# keypad.net
KiCad netlist of a schematic drawn in Altium Designer
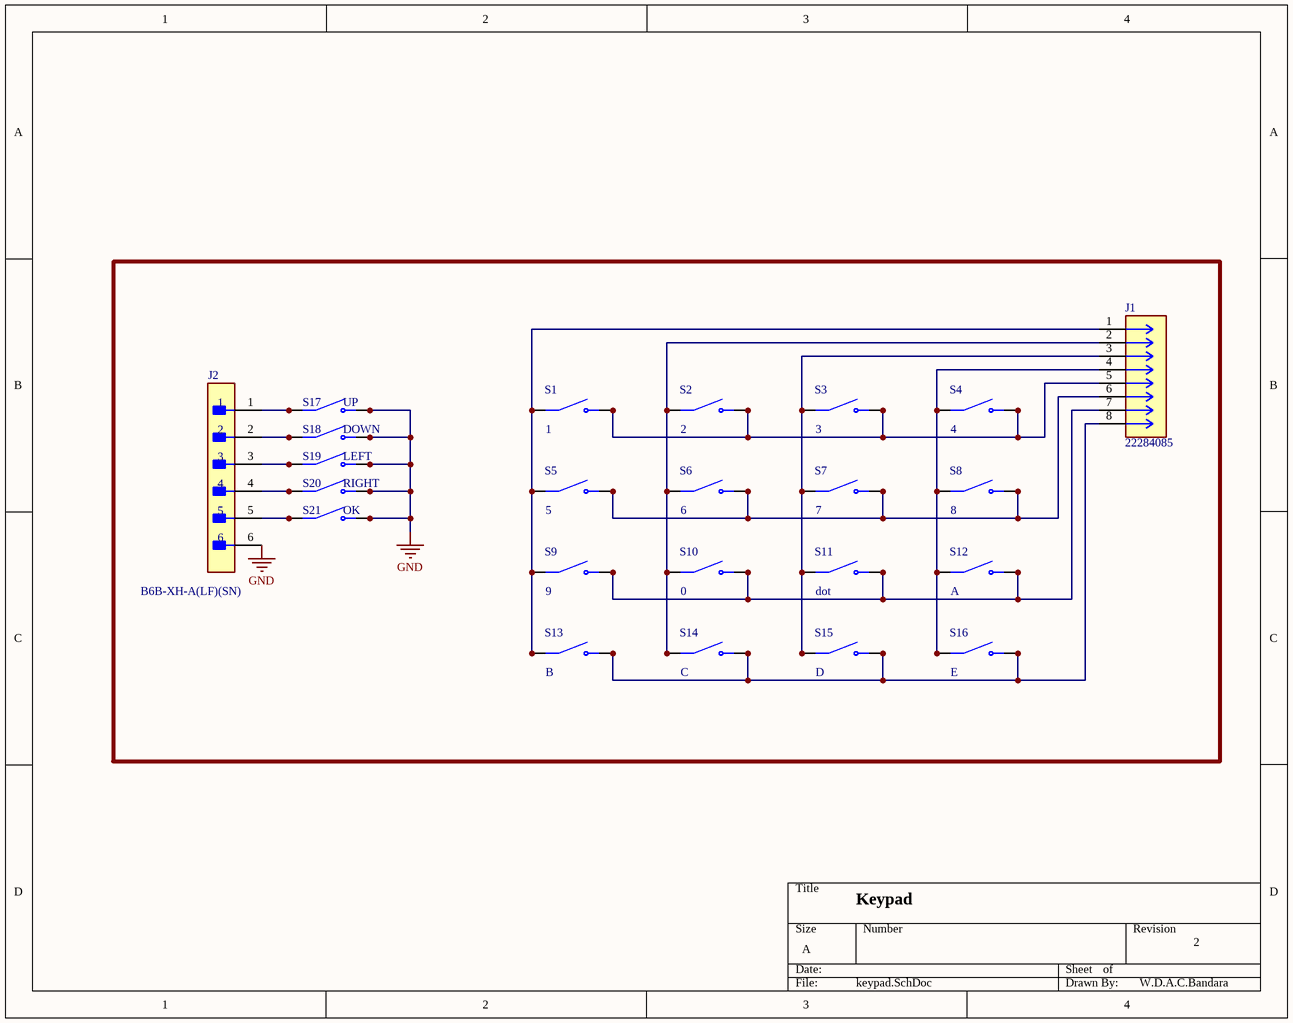
[diagram p0: keypad.SchDoc]

(export (version "E")
  (design (tool "Eeschema 10.0.6"))
  (components
    (comp (ref "J1")
      (value "22284085")
      (footprint "CONN_SD-42375-001_M295_08_MOL")
      (libsource (lib "Achintha Bandara") (part "22284085"))
    )
    (comp (ref "J2")
      (value "B6B-XH-A(LF)(SN)")
      (footprint "FP-B6B-XH-A_LF_SN-MFG")
      (description "CONN HEADER VERT 6POS 2.5MM")
      (libsource (lib "Altium Content Vault") (part "f2cb566baf1c37ab5a3b8e90bbeafd6"))
    )
    (comp (ref "S1")
      (value "1")
      (footprint "SW_B3F-4050")
      (description "Tactile Switch SPST-NO Top Actuated Through Hole")
      (fields (field (name "MP") "B3F-4050") (field (name "MF") "Omron Electronics"))
      (libsource (lib "Achintha Bandara") (part "B3F-4050"))
    )
    (comp (ref "S2")
      (value "2")
      (footprint "SW_B3F-4050")
      (description "Tactile Switch SPST-NO Top Actuated Through Hole")
      (fields (field (name "MP") "B3F-4050") (field (name "MF") "Omron Electronics"))
      (libsource (lib "Achintha Bandara") (part "B3F-4050"))
    )
    (comp (ref "S3")
      (value "3")
      (footprint "SW_B3F-4050")
      (description "Tactile Switch SPST-NO Top Actuated Through Hole")
      (fields (field (name "MP") "B3F-4050") (field (name "MF") "Omron Electronics"))
      (libsource (lib "Achintha Bandara") (part "B3F-4050"))
    )
    (comp (ref "S4")
      (value "4")
      (footprint "SW_B3F-4050")
      (description "Tactile Switch SPST-NO Top Actuated Through Hole")
      (fields (field (name "MP") "B3F-4050") (field (name "MF") "Omron Electronics"))
      (libsource (lib "Achintha Bandara") (part "B3F-4050"))
    )
    (comp (ref "S5")
      (value "5")
      (footprint "SW_B3F-4050")
      (description "Tactile Switch SPST-NO Top Actuated Through Hole")
      (fields (field (name "MP") "B3F-4050") (field (name "MF") "Omron Electronics"))
      (libsource (lib "Achintha Bandara") (part "B3F-4050"))
    )
    (comp (ref "S6")
      (value "6")
      (footprint "SW_B3F-4050")
      (description "Tactile Switch SPST-NO Top Actuated Through Hole")
      (fields (field (name "MP") "B3F-4050") (field (name "MF") "Omron Electronics"))
      (libsource (lib "Achintha Bandara") (part "B3F-4050"))
    )
    (comp (ref "S7")
      (value "7")
      (footprint "SW_B3F-4050")
      (description "Tactile Switch SPST-NO Top Actuated Through Hole")
      (fields (field (name "MP") "B3F-4050") (field (name "MF") "Omron Electronics"))
      (libsource (lib "Achintha Bandara") (part "B3F-4050"))
    )
    (comp (ref "S8")
      (value "8")
      (footprint "SW_B3F-4050")
      (description "Tactile Switch SPST-NO Top Actuated Through Hole")
      (fields (field (name "MP") "B3F-4050") (field (name "MF") "Omron Electronics"))
      (libsource (lib "Achintha Bandara") (part "B3F-4050"))
    )
    (comp (ref "S9")
      (value "9")
      (footprint "SW_B3F-4050")
      (description "Tactile Switch SPST-NO Top Actuated Through Hole")
      (fields (field (name "MP") "B3F-4050") (field (name "MF") "Omron Electronics"))
      (libsource (lib "Achintha Bandara") (part "B3F-4050"))
    )
    (comp (ref "S10")
      (value "0")
      (footprint "SW_B3F-4050")
      (description "Tactile Switch SPST-NO Top Actuated Through Hole")
      (fields (field (name "MP") "B3F-4050") (field (name "MF") "Omron Electronics"))
      (libsource (lib "Achintha Bandara") (part "B3F-4050"))
    )
    (comp (ref "S11")
      (value "dot")
      (footprint "SW_B3F-4050")
      (description "Tactile Switch SPST-NO Top Actuated Through Hole")
      (fields (field (name "MP") "B3F-4050") (field (name "MF") "Omron Electronics"))
      (libsource (lib "Achintha Bandara") (part "B3F-4050"))
    )
    (comp (ref "S12")
      (value "A")
      (footprint "SW_B3F-4050")
      (description "Tactile Switch SPST-NO Top Actuated Through Hole")
      (fields (field (name "MP") "B3F-4050") (field (name "MF") "Omron Electronics"))
      (libsource (lib "Achintha Bandara") (part "B3F-4050"))
    )
    (comp (ref "S13")
      (value "B")
      (footprint "SW_B3F-4050")
      (description "Tactile Switch SPST-NO Top Actuated Through Hole")
      (fields (field (name "MP") "B3F-4050") (field (name "MF") "Omron Electronics"))
      (libsource (lib "Achintha Bandara") (part "B3F-4050"))
    )
    (comp (ref "S14")
      (value "C")
      (footprint "SW_B3F-4050")
      (description "Tactile Switch SPST-NO Top Actuated Through Hole")
      (fields (field (name "MP") "B3F-4050") (field (name "MF") "Omron Electronics"))
      (libsource (lib "Achintha Bandara") (part "B3F-4050"))
    )
    (comp (ref "S15")
      (value "D")
      (footprint "SW_B3F-4050")
      (description "Tactile Switch SPST-NO Top Actuated Through Hole")
      (fields (field (name "MP") "B3F-4050") (field (name "MF") "Omron Electronics"))
      (libsource (lib "Achintha Bandara") (part "B3F-4050"))
    )
    (comp (ref "S16")
      (value "E")
      (footprint "SW_B3F-4050")
      (description "Tactile Switch SPST-NO Top Actuated Through Hole")
      (fields (field (name "MP") "B3F-4050") (field (name "MF") "Omron Electronics"))
      (libsource (lib "Achintha Bandara") (part "B3F-4050"))
    )
    (comp (ref "S17")
      (value "UP")
      (footprint "SW_B3F-4050")
      (description "Tactile Switch SPST-NO Top Actuated Through Hole")
      (fields (field (name "MP") "B3F-4050") (field (name "MF") "Omron Electronics"))
      (libsource (lib "Achintha Bandara") (part "B3F-4050"))
    )
    (comp (ref "S18")
      (value "DOWN")
      (footprint "SW_B3F-4050")
      (description "Tactile Switch SPST-NO Top Actuated Through Hole")
      (fields (field (name "MP") "B3F-4050") (field (name "MF") "Omron Electronics"))
      (libsource (lib "Achintha Bandara") (part "B3F-4050"))
    )
    (comp (ref "S19")
      (value "LEFT")
      (footprint "SW_B3F-4050")
      (description "Tactile Switch SPST-NO Top Actuated Through Hole")
      (fields (field (name "MP") "B3F-4050") (field (name "MF") "Omron Electronics"))
      (libsource (lib "Achintha Bandara") (part "B3F-4050"))
    )
    (comp (ref "S20")
      (value "RIGHT")
      (footprint "SW_B3F-4050")
      (description "Tactile Switch SPST-NO Top Actuated Through Hole")
      (fields (field (name "MP") "B3F-4050") (field (name "MF") "Omron Electronics"))
      (libsource (lib "Achintha Bandara") (part "B3F-4050"))
    )
    (comp (ref "S21")
      (value "OK")
      (footprint "SW_B3F-4050")
      (description "Tactile Switch SPST-NO Top Actuated Through Hole")
      (fields (field (name "MP") "B3F-4050") (field (name "MF") "Omron Electronics"))
      (libsource (lib "Achintha Bandara") (part "B3F-4050"))
    )
  )
  (nets
    (net (code "1") (name "GND") (class "Default")
      (node (ref "J2") (pin "6") (pinfunction "6_6") (pintype "passive"))
      (node (ref "S17") (pin "3") (pinfunction "NO_3") (pintype "passive"))
      (node (ref "S17") (pin "4") (pinfunction "NO_4") (pintype "passive"))
      (node (ref "S18") (pin "3") (pinfunction "NO_3") (pintype "passive"))
      (node (ref "S18") (pin "4") (pinfunction "NO_4") (pintype "passive"))
      (node (ref "S19") (pin "3") (pinfunction "NO_3") (pintype "passive"))
      (node (ref "S19") (pin "4") (pinfunction "NO_4") (pintype "passive"))
      (node (ref "S20") (pin "3") (pinfunction "NO_3") (pintype "passive"))
      (node (ref "S20") (pin "4") (pinfunction "NO_4") (pintype "passive"))
      (node (ref "S21") (pin "3") (pinfunction "NO_3") (pintype "passive"))
      (node (ref "S21") (pin "4") (pinfunction "NO_4") (pintype "passive"))
    )
    (net (code "2") (name "Net-(J1-Pad1)") (class "Default")
      (node (ref "J1") (pin "1") (pinfunction "1_1") (pintype "passive"))
      (node (ref "S1") (pin "1") (pinfunction "COM_1") (pintype "passive"))
      (node (ref "S1") (pin "2") (pinfunction "COM_2") (pintype "passive"))
      (node (ref "S13") (pin "1") (pinfunction "COM_1") (pintype "passive"))
      (node (ref "S13") (pin "2") (pinfunction "COM_2") (pintype "passive"))
      (node (ref "S5") (pin "1") (pinfunction "COM_1") (pintype "passive"))
      (node (ref "S5") (pin "2") (pinfunction "COM_2") (pintype "passive"))
      (node (ref "S9") (pin "1") (pinfunction "COM_1") (pintype "passive"))
      (node (ref "S9") (pin "2") (pinfunction "COM_2") (pintype "passive"))
    )
    (net (code "3") (name "Net-(J1-Pad2)") (class "Default")
      (node (ref "J1") (pin "2") (pinfunction "2_2") (pintype "passive"))
      (node (ref "S10") (pin "1") (pinfunction "COM_1") (pintype "passive"))
      (node (ref "S10") (pin "2") (pinfunction "COM_2") (pintype "passive"))
      (node (ref "S14") (pin "1") (pinfunction "COM_1") (pintype "passive"))
      (node (ref "S14") (pin "2") (pinfunction "COM_2") (pintype "passive"))
      (node (ref "S2") (pin "1") (pinfunction "COM_1") (pintype "passive"))
      (node (ref "S2") (pin "2") (pinfunction "COM_2") (pintype "passive"))
      (node (ref "S6") (pin "1") (pinfunction "COM_1") (pintype "passive"))
      (node (ref "S6") (pin "2") (pinfunction "COM_2") (pintype "passive"))
    )
    (net (code "4") (name "Net-(J1-Pad3)") (class "Default")
      (node (ref "J1") (pin "3") (pinfunction "3_3") (pintype "passive"))
      (node (ref "S11") (pin "1") (pinfunction "COM_1") (pintype "passive"))
      (node (ref "S11") (pin "2") (pinfunction "COM_2") (pintype "passive"))
      (node (ref "S15") (pin "1") (pinfunction "COM_1") (pintype "passive"))
      (node (ref "S15") (pin "2") (pinfunction "COM_2") (pintype "passive"))
      (node (ref "S3") (pin "1") (pinfunction "COM_1") (pintype "passive"))
      (node (ref "S3") (pin "2") (pinfunction "COM_2") (pintype "passive"))
      (node (ref "S7") (pin "1") (pinfunction "COM_1") (pintype "passive"))
      (node (ref "S7") (pin "2") (pinfunction "COM_2") (pintype "passive"))
    )
    (net (code "5") (name "Net-(J1-Pad4)") (class "Default")
      (node (ref "J1") (pin "4") (pinfunction "4_4") (pintype "passive"))
      (node (ref "S12") (pin "1") (pinfunction "COM_1") (pintype "passive"))
      (node (ref "S12") (pin "2") (pinfunction "COM_2") (pintype "passive"))
      (node (ref "S16") (pin "1") (pinfunction "COM_1") (pintype "passive"))
      (node (ref "S16") (pin "2") (pinfunction "COM_2") (pintype "passive"))
      (node (ref "S4") (pin "1") (pinfunction "COM_1") (pintype "passive"))
      (node (ref "S4") (pin "2") (pinfunction "COM_2") (pintype "passive"))
      (node (ref "S8") (pin "1") (pinfunction "COM_1") (pintype "passive"))
      (node (ref "S8") (pin "2") (pinfunction "COM_2") (pintype "passive"))
    )
    (net (code "6") (name "Net-(J1-Pad5)") (class "Default")
      (node (ref "J1") (pin "5") (pinfunction "5_5") (pintype "passive"))
      (node (ref "S1") (pin "3") (pinfunction "NO_3") (pintype "passive"))
      (node (ref "S1") (pin "4") (pinfunction "NO_4") (pintype "passive"))
      (node (ref "S2") (pin "3") (pinfunction "NO_3") (pintype "passive"))
      (node (ref "S2") (pin "4") (pinfunction "NO_4") (pintype "passive"))
      (node (ref "S3") (pin "3") (pinfunction "NO_3") (pintype "passive"))
      (node (ref "S3") (pin "4") (pinfunction "NO_4") (pintype "passive"))
      (node (ref "S4") (pin "3") (pinfunction "NO_3") (pintype "passive"))
      (node (ref "S4") (pin "4") (pinfunction "NO_4") (pintype "passive"))
    )
    (net (code "7") (name "Net-(J1-Pad6)") (class "Default")
      (node (ref "J1") (pin "6") (pinfunction "6_6") (pintype "passive"))
      (node (ref "S5") (pin "3") (pinfunction "NO_3") (pintype "passive"))
      (node (ref "S5") (pin "4") (pinfunction "NO_4") (pintype "passive"))
      (node (ref "S6") (pin "3") (pinfunction "NO_3") (pintype "passive"))
      (node (ref "S6") (pin "4") (pinfunction "NO_4") (pintype "passive"))
      (node (ref "S7") (pin "3") (pinfunction "NO_3") (pintype "passive"))
      (node (ref "S7") (pin "4") (pinfunction "NO_4") (pintype "passive"))
      (node (ref "S8") (pin "3") (pinfunction "NO_3") (pintype "passive"))
      (node (ref "S8") (pin "4") (pinfunction "NO_4") (pintype "passive"))
    )
    (net (code "8") (name "Net-(J1-Pad7)") (class "Default")
      (node (ref "J1") (pin "7") (pinfunction "7_7") (pintype "passive"))
      (node (ref "S10") (pin "3") (pinfunction "NO_3") (pintype "passive"))
      (node (ref "S10") (pin "4") (pinfunction "NO_4") (pintype "passive"))
      (node (ref "S11") (pin "3") (pinfunction "NO_3") (pintype "passive"))
      (node (ref "S11") (pin "4") (pinfunction "NO_4") (pintype "passive"))
      (node (ref "S12") (pin "3") (pinfunction "NO_3") (pintype "passive"))
      (node (ref "S12") (pin "4") (pinfunction "NO_4") (pintype "passive"))
      (node (ref "S9") (pin "3") (pinfunction "NO_3") (pintype "passive"))
      (node (ref "S9") (pin "4") (pinfunction "NO_4") (pintype "passive"))
    )
    (net (code "9") (name "Net-(J1-Pad8)") (class "Default")
      (node (ref "J1") (pin "8") (pinfunction "8_8") (pintype "passive"))
      (node (ref "S13") (pin "3") (pinfunction "NO_3") (pintype "passive"))
      (node (ref "S13") (pin "4") (pinfunction "NO_4") (pintype "passive"))
      (node (ref "S14") (pin "3") (pinfunction "NO_3") (pintype "passive"))
      (node (ref "S14") (pin "4") (pinfunction "NO_4") (pintype "passive"))
      (node (ref "S15") (pin "3") (pinfunction "NO_3") (pintype "passive"))
      (node (ref "S15") (pin "4") (pinfunction "NO_4") (pintype "passive"))
      (node (ref "S16") (pin "3") (pinfunction "NO_3") (pintype "passive"))
      (node (ref "S16") (pin "4") (pinfunction "NO_4") (pintype "passive"))
    )
    (net (code "10") (name "Net-(J2-Pad1)") (class "Default")
      (node (ref "J2") (pin "1") (pinfunction "1_1") (pintype "passive"))
      (node (ref "S17") (pin "1") (pinfunction "COM_1") (pintype "passive"))
      (node (ref "S17") (pin "2") (pinfunction "COM_2") (pintype "passive"))
    )
    (net (code "11") (name "Net-(J2-Pad2)") (class "Default")
      (node (ref "J2") (pin "2") (pinfunction "2_2") (pintype "passive"))
      (node (ref "S18") (pin "1") (pinfunction "COM_1") (pintype "passive"))
      (node (ref "S18") (pin "2") (pinfunction "COM_2") (pintype "passive"))
    )
    (net (code "12") (name "Net-(J2-Pad3)") (class "Default")
      (node (ref "J2") (pin "3") (pinfunction "3_3") (pintype "passive"))
      (node (ref "S19") (pin "1") (pinfunction "COM_1") (pintype "passive"))
      (node (ref "S19") (pin "2") (pinfunction "COM_2") (pintype "passive"))
    )
    (net (code "13") (name "Net-(J2-Pad4)") (class "Default")
      (node (ref "J2") (pin "4") (pinfunction "4_4") (pintype "passive"))
      (node (ref "S20") (pin "1") (pinfunction "COM_1") (pintype "passive"))
      (node (ref "S20") (pin "2") (pinfunction "COM_2") (pintype "passive"))
    )
    (net (code "14") (name "Net-(J2-Pad5)") (class "Default")
      (node (ref "J2") (pin "5") (pinfunction "5_5") (pintype "passive"))
      (node (ref "S21") (pin "1") (pinfunction "COM_1") (pintype "passive"))
      (node (ref "S21") (pin "2") (pinfunction "COM_2") (pintype "passive"))
    )
  )
)
